# atmegaArduino.net
KiCad netlist of a schematic drawn in EAGLE
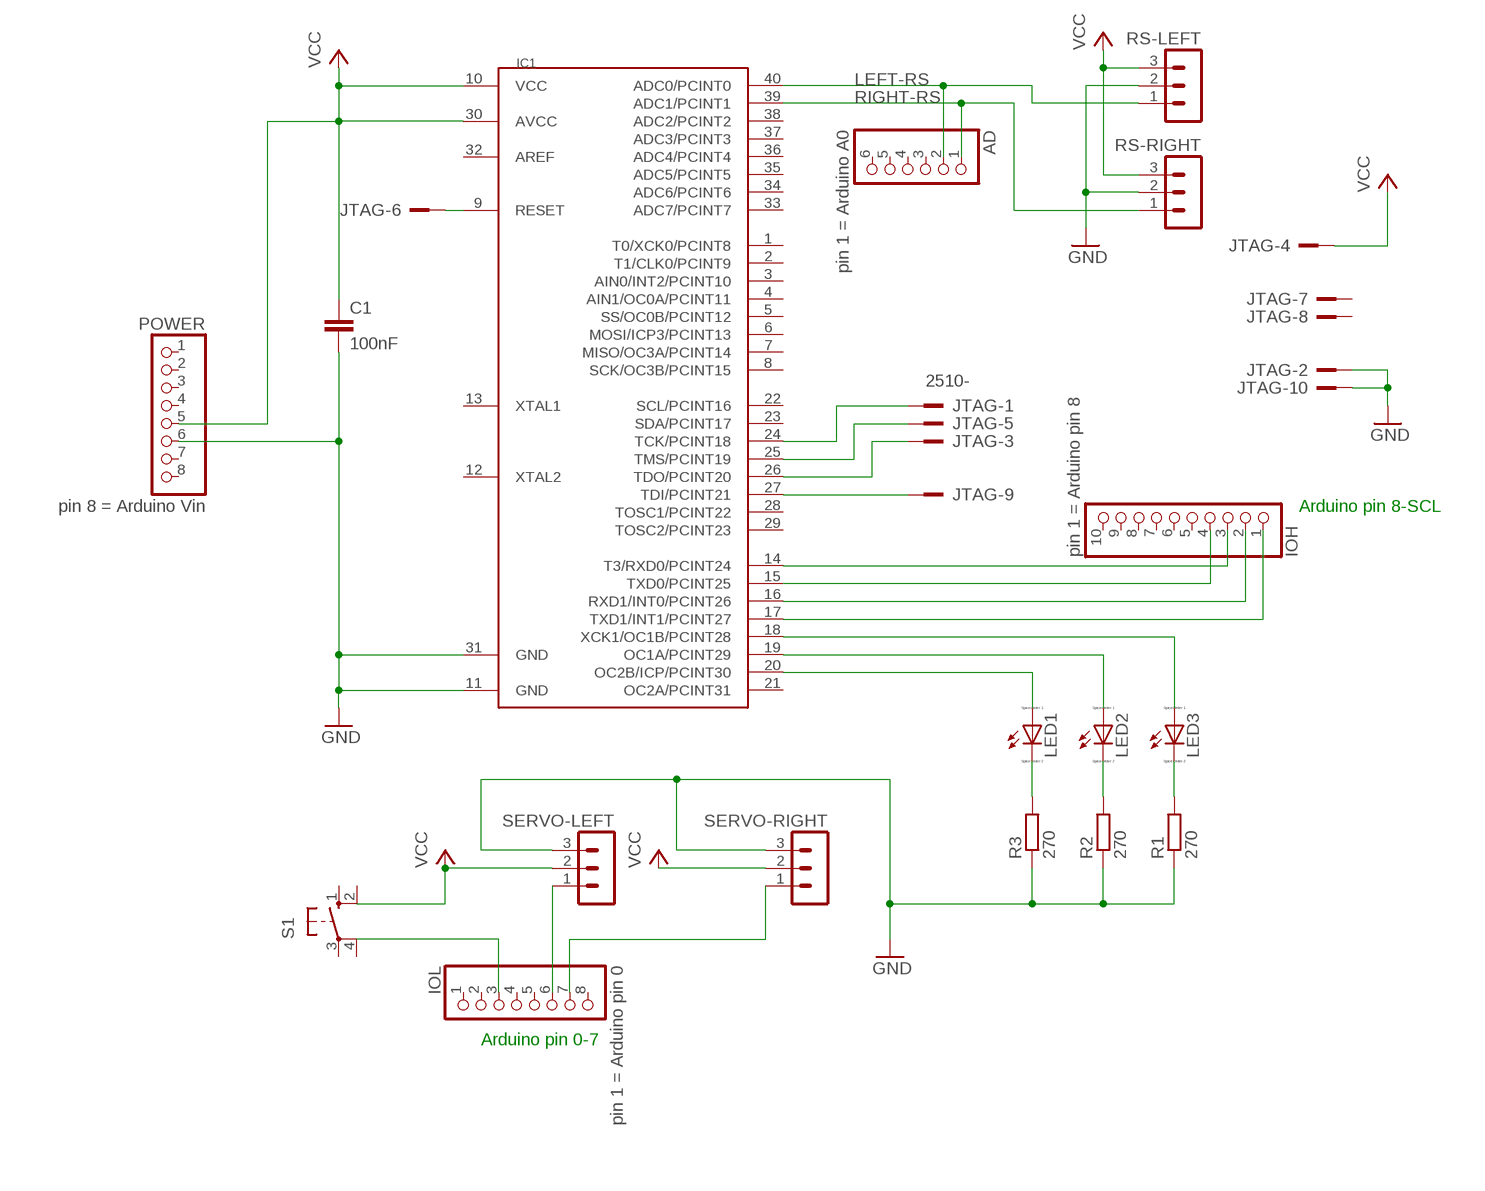
[diagram p0: schematic, sheet 1]

(export (version "E")
  (design (tool "Eeschema 10.0.6"))
  (components
    (comp (ref "AD")
      (value "pin 1 = Arduino A0")
      (footprint "eagle-import:1X06_90")
      (libsource (lib "eagle-import") (part "PINHD-1X6/90"))
    )
    (comp (ref "C1")
      (value "100nF")
      (footprint "eagle-import:C050-025X075")
      (libsource (lib "eagle-import") (part "C-EU050-025X075"))
    )
    (comp (ref "IC1")
      (value "MEGA1284P")
      (footprint "eagle-import:DIL40")
      (libsource (lib "eagle-import") (part "MEGA1284P"))
    )
    (comp (ref "IOH")
      (value "pin 1 = Arduino pin 8")
      (footprint "eagle-import:1X10_90")
      (libsource (lib "eagle-import") (part "PINHD-1X10/90"))
    )
    (comp (ref "IOL")
      (value "pin 1 = Arduino pin 0")
      (footprint "eagle-import:1X08_90")
      (libsource (lib "eagle-import") (part "PINHD-1X8/90"))
    )
    (comp (ref "JTAG")
      (value "2510-")
      (footprint "eagle-import:PAK100_2500-10")
      (fields (field (name "MF") "3M") (field (name "MPN") "2510-6002UB"))
      (libsource (lib "eagle-import") (part "2510-"))
    )
    (comp (ref "LED1")
      (value "LED_ELD260")
      (footprint "eagle-import:LED_LD260")
      (libsource (lib "eagle-import") (part "LED_ELD260"))
    )
    (comp (ref "LED2")
      (value "LED_ELD260")
      (footprint "eagle-import:LED_LD260")
      (libsource (lib "eagle-import") (part "LED_ELD260"))
    )
    (comp (ref "LED3")
      (value "LED_ELD260")
      (footprint "eagle-import:LED_LD260")
      (libsource (lib "eagle-import") (part "LED_ELD260"))
    )
    (comp (ref "POWER")
      (value "pin 8 = Arduino Vin")
      (footprint "eagle-import:1X08_90")
      (libsource (lib "eagle-import") (part "PINHD-1X8/90"))
    )
    (comp (ref "R1")
      (value "270")
      (footprint "eagle-import:0204_5")
      (libsource (lib "eagle-import") (part "R-EU_0204/5"))
    )
    (comp (ref "R2")
      (value "270")
      (footprint "eagle-import:0204_5")
      (libsource (lib "eagle-import") (part "R-EU_0204/5"))
    )
    (comp (ref "R3")
      (value "270")
      (footprint "eagle-import:0204_5")
      (libsource (lib "eagle-import") (part "R-EU_0204/5"))
    )
    (comp (ref "RS-LEFT")
      (value "MA03-1")
      (footprint "eagle-import:MA03-1")
      (libsource (lib "eagle-import") (part "MA03-1"))
    )
    (comp (ref "RS-RIGHT")
      (value "MA03-1")
      (footprint "eagle-import:MA03-1")
      (libsource (lib "eagle-import") (part "MA03-1"))
    )
    (comp (ref "S1")
      (value "10-XX")
      (footprint "eagle-import:B3F-10XX")
      (fields (field (name "MPN") "B3F-1000"))
      (libsource (lib "eagle-import") (part "10-XX"))
    )
    (comp (ref "SERVO-LEFT")
      (value "MA03-1")
      (footprint "eagle-import:MA03-1")
      (libsource (lib "eagle-import") (part "MA03-1"))
    )
    (comp (ref "SERVO-RIGHT")
      (value "MA03-1")
      (footprint "eagle-import:MA03-1")
      (libsource (lib "eagle-import") (part "MA03-1"))
    )
  )
  (nets
    (net (code "1") (name "/LEFT-RS") (class "Default")
      (node (ref "AD") (pin "2") (pinfunction "2_2") (pintype "passive"))
      (node (ref "IC1") (pin "40") (pinfunction "ADC0/PCINT0_40") (pintype "bidirectional"))
      (node (ref "RS-LEFT") (pin "1") (pinfunction "1_1") (pintype "passive"))
    )
    (net (code "2") (name "/RIGHT-RS") (class "Default")
      (node (ref "AD") (pin "1") (pinfunction "1_1") (pintype "passive"))
      (node (ref "IC1") (pin "39") (pinfunction "ADC1/PCINT1_39") (pintype "bidirectional"))
      (node (ref "RS-RIGHT") (pin "1") (pinfunction "1_1") (pintype "passive"))
    )
    (net (code "3") (name "GND") (class "Default")
      (node (ref "C1") (pin "2") (pinfunction "2_2") (pintype "passive"))
      (node (ref "IC1") (pin "11") (pinfunction "GND_11") (pintype "bidirectional"))
      (node (ref "IC1") (pin "31") (pinfunction "GND_31") (pintype "bidirectional"))
      (node (ref "JTAG") (pin "10") (pinfunction "KL_10") (pintype "passive"))
      (node (ref "JTAG") (pin "2") (pinfunction "KL_2") (pintype "passive"))
      (node (ref "POWER") (pin "6") (pinfunction "6_6") (pintype "passive"))
      (node (ref "R1") (pin "1") (pinfunction "1_1") (pintype "passive"))
      (node (ref "R2") (pin "1") (pinfunction "1_1") (pintype "passive"))
      (node (ref "R3") (pin "1") (pinfunction "1_1") (pintype "passive"))
      (node (ref "RS-LEFT") (pin "2") (pinfunction "2_2") (pintype "passive"))
      (node (ref "RS-RIGHT") (pin "2") (pinfunction "2_2") (pintype "passive"))
      (node (ref "SERVO-LEFT") (pin "3") (pinfunction "3_3") (pintype "passive"))
      (node (ref "SERVO-RIGHT") (pin "3") (pinfunction "3_3") (pintype "passive"))
    )
    (net (code "4") (name "Net-(IC1-OC1A{slash}PCINT29)") (class "Default")
      (node (ref "IC1") (pin "19") (pinfunction "OC1A/PCINT29_19") (pintype "bidirectional"))
      (node (ref "LED2") (pin "A") (pinfunction "A_A") (pintype "passive"))
    )
    (net (code "5") (name "Net-(IC1-OC2B{slash}ICP{slash}PCINT30)") (class "Default")
      (node (ref "IC1") (pin "20") (pinfunction "OC2B/ICP/PCINT30_20") (pintype "bidirectional"))
      (node (ref "LED1") (pin "A") (pinfunction "A_A") (pintype "passive"))
    )
    (net (code "6") (name "Net-(IC1-RESET)") (class "Default")
      (node (ref "IC1") (pin "9") (pinfunction "RESET_9") (pintype "bidirectional"))
      (node (ref "JTAG") (pin "6") (pinfunction "KL_6") (pintype "passive"))
    )
    (net (code "7") (name "Net-(IC1-RXD1{slash}INT0{slash}PCINT26)") (class "Default")
      (node (ref "IC1") (pin "16") (pinfunction "RXD1/INT0/PCINT26_16") (pintype "bidirectional"))
      (node (ref "IOH") (pin "2") (pinfunction "2_2") (pintype "passive"))
    )
    (net (code "8") (name "Net-(IC1-T3{slash}RXD0{slash}PCINT24)") (class "Default")
      (node (ref "IC1") (pin "14") (pinfunction "T3/RXD0/PCINT24_14") (pintype "bidirectional"))
      (node (ref "IOH") (pin "3") (pinfunction "3_3") (pintype "passive"))
    )
    (net (code "9") (name "Net-(IC1-TCK{slash}PCINT18)") (class "Default")
      (node (ref "IC1") (pin "24") (pinfunction "TCK/PCINT18_24") (pintype "bidirectional"))
      (node (ref "JTAG") (pin "1") (pinfunction "KL_1") (pintype "passive"))
    )
    (net (code "10") (name "Net-(IC1-TDI{slash}PCINT21)") (class "Default")
      (node (ref "IC1") (pin "27") (pinfunction "TDI/PCINT21_27") (pintype "bidirectional"))
      (node (ref "JTAG") (pin "9") (pinfunction "KL_9") (pintype "passive"))
    )
    (net (code "11") (name "Net-(IC1-TDO{slash}PCINT20)") (class "Default")
      (node (ref "IC1") (pin "26") (pinfunction "TDO/PCINT20_26") (pintype "bidirectional"))
      (node (ref "JTAG") (pin "3") (pinfunction "KL_3") (pintype "passive"))
    )
    (net (code "12") (name "Net-(IC1-TMS{slash}PCINT19)") (class "Default")
      (node (ref "IC1") (pin "25") (pinfunction "TMS/PCINT19_25") (pintype "bidirectional"))
      (node (ref "JTAG") (pin "5") (pinfunction "KL_5") (pintype "passive"))
    )
    (net (code "13") (name "Net-(IC1-TXD0{slash}PCINT25)") (class "Default")
      (node (ref "IC1") (pin "15") (pinfunction "TXD0/PCINT25_15") (pintype "bidirectional"))
      (node (ref "IOH") (pin "4") (pinfunction "4_4") (pintype "passive"))
    )
    (net (code "14") (name "Net-(IC1-TXD1{slash}INT1{slash}PCINT27)") (class "Default")
      (node (ref "IC1") (pin "17") (pinfunction "TXD1/INT1/PCINT27_17") (pintype "bidirectional"))
      (node (ref "IOH") (pin "1") (pinfunction "1_1") (pintype "passive"))
    )
    (net (code "15") (name "Net-(IC1-XCK1{slash}OC1B{slash}PCINT28)") (class "Default")
      (node (ref "IC1") (pin "18") (pinfunction "XCK1/OC1B/PCINT28_18") (pintype "bidirectional"))
      (node (ref "LED3") (pin "A") (pinfunction "A_A") (pintype "passive"))
    )
    (net (code "16") (name "Net-(IOL-Pad6)") (class "Default")
      (node (ref "IOL") (pin "6") (pinfunction "6_6") (pintype "passive"))
      (node (ref "SERVO-LEFT") (pin "1") (pinfunction "1_1") (pintype "passive"))
    )
    (net (code "17") (name "Net-(IOL-Pad7)") (class "Default")
      (node (ref "IOL") (pin "7") (pinfunction "7_7") (pintype "passive"))
      (node (ref "SERVO-RIGHT") (pin "1") (pinfunction "1_1") (pintype "passive"))
    )
    (net (code "18") (name "Net-(LED1-C)") (class "Default")
      (node (ref "LED1") (pin "K") (pinfunction "C_K") (pintype "passive"))
      (node (ref "R3") (pin "2") (pinfunction "2_2") (pintype "passive"))
    )
    (net (code "19") (name "Net-(LED2-C)") (class "Default")
      (node (ref "LED2") (pin "K") (pinfunction "C_K") (pintype "passive"))
      (node (ref "R2") (pin "2") (pinfunction "2_2") (pintype "passive"))
    )
    (net (code "20") (name "Net-(LED3-C)") (class "Default")
      (node (ref "LED3") (pin "K") (pinfunction "C_K") (pintype "passive"))
      (node (ref "R1") (pin "2") (pinfunction "2_2") (pintype "passive"))
    )
    (net (code "21") (name "VCC") (class "Default")
      (node (ref "C1") (pin "1") (pinfunction "1_1") (pintype "passive"))
      (node (ref "IC1") (pin "10") (pinfunction "VCC_10") (pintype "bidirectional"))
      (node (ref "IC1") (pin "30") (pinfunction "AVCC_30") (pintype "bidirectional"))
      (node (ref "JTAG") (pin "4") (pinfunction "KL_4") (pintype "passive"))
      (node (ref "POWER") (pin "5") (pinfunction "5_5") (pintype "passive"))
      (node (ref "RS-LEFT") (pin "3") (pinfunction "3_3") (pintype "passive"))
      (node (ref "RS-RIGHT") (pin "3") (pinfunction "3_3") (pintype "passive"))
      (node (ref "SERVO-LEFT") (pin "2") (pinfunction "2_2") (pintype "passive"))
      (node (ref "SERVO-RIGHT") (pin "2") (pinfunction "2_2") (pintype "passive"))
    )
    (net (code "22") (name "unconnected-(AD-Pad3)") (class "Default")
      (node (ref "AD") (pin "3") (pinfunction "3_3") (pintype "passive"))
    )
    (net (code "23") (name "unconnected-(AD-Pad4)") (class "Default")
      (node (ref "AD") (pin "4") (pinfunction "4_4") (pintype "passive"))
    )
    (net (code "24") (name "unconnected-(AD-Pad5)") (class "Default")
      (node (ref "AD") (pin "5") (pinfunction "5_5") (pintype "passive"))
    )
    (net (code "25") (name "unconnected-(AD-Pad6)") (class "Default")
      (node (ref "AD") (pin "6") (pinfunction "6_6") (pintype "passive"))
    )
    (net (code "26") (name "unconnected-(IC1-ADC2{slash}PCINT2-Pad38)") (class "Default")
      (node (ref "IC1") (pin "38") (pinfunction "ADC2/PCINT2_38") (pintype "bidirectional"))
    )
    (net (code "27") (name "unconnected-(IC1-ADC3{slash}PCINT3-Pad37)") (class "Default")
      (node (ref "IC1") (pin "37") (pinfunction "ADC3/PCINT3_37") (pintype "bidirectional"))
    )
    (net (code "28") (name "unconnected-(IC1-ADC4{slash}PCINT4-Pad36)") (class "Default")
      (node (ref "IC1") (pin "36") (pinfunction "ADC4/PCINT4_36") (pintype "bidirectional"))
    )
    (net (code "29") (name "unconnected-(IC1-ADC5{slash}PCINT5-Pad35)") (class "Default")
      (node (ref "IC1") (pin "35") (pinfunction "ADC5/PCINT5_35") (pintype "bidirectional"))
    )
    (net (code "30") (name "unconnected-(IC1-ADC6{slash}PCINT6-Pad34)") (class "Default")
      (node (ref "IC1") (pin "34") (pinfunction "ADC6/PCINT6_34") (pintype "bidirectional"))
    )
    (net (code "31") (name "unconnected-(IC1-ADC7{slash}PCINT7-Pad33)") (class "Default")
      (node (ref "IC1") (pin "33") (pinfunction "ADC7/PCINT7_33") (pintype "bidirectional"))
    )
    (net (code "32") (name "unconnected-(IC1-AIN0{slash}INT2{slash}PCINT10-Pad3)") (class "Default")
      (node (ref "IC1") (pin "3") (pinfunction "AIN0/INT2/PCINT10_3") (pintype "bidirectional"))
    )
    (net (code "33") (name "unconnected-(IC1-AIN1{slash}OC0A{slash}PCINT11-Pad4)") (class "Default")
      (node (ref "IC1") (pin "4") (pinfunction "AIN1/OC0A/PCINT11_4") (pintype "bidirectional"))
    )
    (net (code "34") (name "unconnected-(IC1-AREF-Pad32)") (class "Default")
      (node (ref "IC1") (pin "32") (pinfunction "AREF_32") (pintype "bidirectional"))
    )
    (net (code "35") (name "unconnected-(IC1-MISO{slash}OC3A{slash}PCINT14-Pad7)") (class "Default")
      (node (ref "IC1") (pin "7") (pinfunction "MISO/OC3A/PCINT14_7") (pintype "bidirectional"))
    )
    (net (code "36") (name "unconnected-(IC1-MOSI{slash}ICP3{slash}PCINT13-Pad6)") (class "Default")
      (node (ref "IC1") (pin "6") (pinfunction "MOSI/ICP3/PCINT13_6") (pintype "bidirectional"))
    )
    (net (code "37") (name "unconnected-(IC1-OC2A{slash}PCINT31-Pad21)") (class "Default")
      (node (ref "IC1") (pin "21") (pinfunction "OC2A/PCINT31_21") (pintype "bidirectional"))
    )
    (net (code "38") (name "unconnected-(IC1-SCK{slash}OC3B{slash}PCINT15-Pad8)") (class "Default")
      (node (ref "IC1") (pin "8") (pinfunction "SCK/OC3B/PCINT15_8") (pintype "bidirectional"))
    )
    (net (code "39") (name "unconnected-(IC1-SCL{slash}PCINT16-Pad22)") (class "Default")
      (node (ref "IC1") (pin "22") (pinfunction "SCL/PCINT16_22") (pintype "bidirectional"))
    )
    (net (code "40") (name "unconnected-(IC1-SDA{slash}PCINT17-Pad23)") (class "Default")
      (node (ref "IC1") (pin "23") (pinfunction "SDA/PCINT17_23") (pintype "bidirectional"))
    )
    (net (code "41") (name "unconnected-(IC1-SS{slash}OC0B{slash}PCINT12-Pad5)") (class "Default")
      (node (ref "IC1") (pin "5") (pinfunction "SS/OC0B/PCINT12_5") (pintype "bidirectional"))
    )
    (net (code "42") (name "unconnected-(IC1-T0{slash}XCK0{slash}PCINT8-Pad1)") (class "Default")
      (node (ref "IC1") (pin "1") (pinfunction "T0/XCK0/PCINT8_1") (pintype "bidirectional"))
    )
    (net (code "43") (name "unconnected-(IC1-T1{slash}CLK0{slash}PCINT9-Pad2)") (class "Default")
      (node (ref "IC1") (pin "2") (pinfunction "T1/CLK0/PCINT9_2") (pintype "bidirectional"))
    )
    (net (code "44") (name "unconnected-(IC1-TOSC1{slash}PCINT22-Pad28)") (class "Default")
      (node (ref "IC1") (pin "28") (pinfunction "TOSC1/PCINT22_28") (pintype "bidirectional"))
    )
    (net (code "45") (name "unconnected-(IC1-TOSC2{slash}PCINT23-Pad29)") (class "Default")
      (node (ref "IC1") (pin "29") (pinfunction "TOSC2/PCINT23_29") (pintype "bidirectional"))
    )
    (net (code "46") (name "unconnected-(IC1-XTAL1-Pad13)") (class "Default")
      (node (ref "IC1") (pin "13") (pinfunction "XTAL1_13") (pintype "bidirectional"))
    )
    (net (code "47") (name "unconnected-(IC1-XTAL2-Pad12)") (class "Default")
      (node (ref "IC1") (pin "12") (pinfunction "XTAL2_12") (pintype "bidirectional"))
    )
    (net (code "48") (name "unconnected-(IOH-Pad5)") (class "Default")
      (node (ref "IOH") (pin "5") (pinfunction "5_5") (pintype "passive"))
    )
    (net (code "49") (name "unconnected-(IOH-Pad6)") (class "Default")
      (node (ref "IOH") (pin "6") (pinfunction "6_6") (pintype "passive"))
    )
    (net (code "50") (name "unconnected-(IOH-Pad7)") (class "Default")
      (node (ref "IOH") (pin "7") (pinfunction "7_7") (pintype "passive"))
    )
    (net (code "51") (name "unconnected-(IOH-Pad8)") (class "Default")
      (node (ref "IOH") (pin "8") (pinfunction "8_8") (pintype "passive"))
    )
    (net (code "52") (name "unconnected-(IOH-Pad9)") (class "Default")
      (node (ref "IOH") (pin "9") (pinfunction "9_9") (pintype "passive"))
    )
    (net (code "53") (name "unconnected-(IOH-Pad10)") (class "Default")
      (node (ref "IOH") (pin "10") (pinfunction "10_10") (pintype "passive"))
    )
    (net (code "54") (name "unconnected-(IOL-Pad1)") (class "Default")
      (node (ref "IOL") (pin "1") (pinfunction "1_1") (pintype "passive"))
    )
    (net (code "55") (name "unconnected-(IOL-Pad2)") (class "Default")
      (node (ref "IOL") (pin "2") (pinfunction "2_2") (pintype "passive"))
    )
    (net (code "56") (name "unconnected-(IOL-Pad3)") (class "Default")
      (node (ref "IOL") (pin "3") (pinfunction "3_3") (pintype "passive"))
    )
    (net (code "57") (name "unconnected-(IOL-Pad4)") (class "Default")
      (node (ref "IOL") (pin "4") (pinfunction "4_4") (pintype "passive"))
    )
    (net (code "58") (name "unconnected-(IOL-Pad5)") (class "Default")
      (node (ref "IOL") (pin "5") (pinfunction "5_5") (pintype "passive"))
    )
    (net (code "59") (name "unconnected-(IOL-Pad8)") (class "Default")
      (node (ref "IOL") (pin "8") (pinfunction "8_8") (pintype "passive"))
    )
    (net (code "60") (name "unconnected-(JTAGH-KL-Pad7)") (class "Default")
      (node (ref "JTAG") (pin "7") (pinfunction "KL_7") (pintype "passive"))
    )
    (net (code "61") (name "unconnected-(JTAGI-KL-Pad8)") (class "Default")
      (node (ref "JTAG") (pin "8") (pinfunction "KL_8") (pintype "passive"))
    )
    (net (code "62") (name "unconnected-(POWER-Pad1)") (class "Default")
      (node (ref "POWER") (pin "1") (pinfunction "1_1") (pintype "passive"))
    )
    (net (code "63") (name "unconnected-(POWER-Pad2)") (class "Default")
      (node (ref "POWER") (pin "2") (pinfunction "2_2") (pintype "passive"))
    )
    (net (code "64") (name "unconnected-(POWER-Pad3)") (class "Default")
      (node (ref "POWER") (pin "3") (pinfunction "3_3") (pintype "passive"))
    )
    (net (code "65") (name "unconnected-(POWER-Pad4)") (class "Default")
      (node (ref "POWER") (pin "4") (pinfunction "4_4") (pintype "passive"))
    )
    (net (code "66") (name "unconnected-(POWER-Pad7)") (class "Default")
      (node (ref "POWER") (pin "7") (pinfunction "7_7") (pintype "passive"))
    )
    (net (code "67") (name "unconnected-(POWER-Pad8)") (class "Default")
      (node (ref "POWER") (pin "8") (pinfunction "8_8") (pintype "passive"))
    )
    (net (code "68") (name "unconnected-(S1-P-Pad3)") (class "Default")
      (node (ref "S1") (pin "3") (pinfunction "P_3") (pintype "passive"))
    )
    (net (code "69") (name "unconnected-(S1-P1-Pad4)") (class "Default")
      (node (ref "S1") (pin "4") (pinfunction "P1_4") (pintype "passive"))
    )
    (net (code "70") (name "unconnected-(S1-S-Pad1)") (class "Default")
      (node (ref "S1") (pin "1") (pinfunction "S_1") (pintype "passive"))
    )
    (net (code "71") (name "unconnected-(S1-S1-Pad2)") (class "Default")
      (node (ref "S1") (pin "2") (pinfunction "S1_2") (pintype "passive"))
    )
  )
)
